# Connectors.net
KiCad netlist of a schematic drawn in Altium Designer
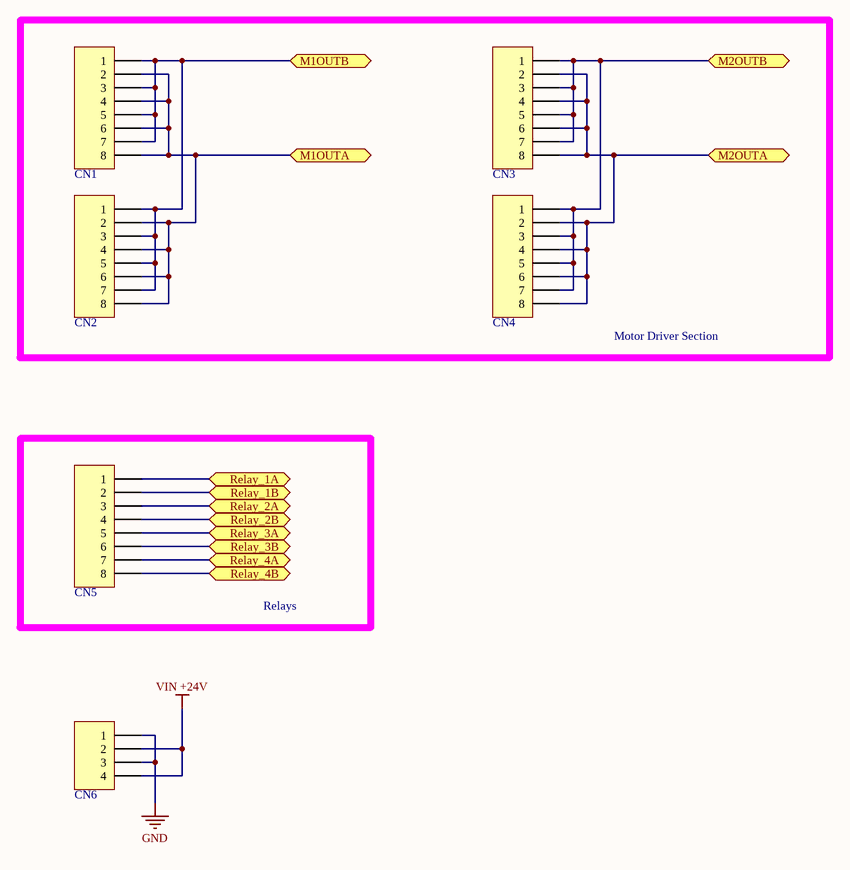
[diagram p0: Connectors.SchDoc]

(export (version "E")
  (design (tool "Eeschema 10.0.6"))
  (components
    (comp (ref "CN1")
      (value "Connector 4973-08TRNLF")
      (footprint "Connector 4973-08TRNLF")
      (description "Connector 8-Pin, 90 degree, 3.5mm")
      (libsource (lib "Erdem_05112012") (part "Connector 4973-08TRNLF"))
    )
    (comp (ref "CN2")
      (value "Connector 4973-08TRNLF")
      (footprint "Connector 4973-08TRNLF")
      (description "Connector 8-Pin, 90 degree, 3.5mm")
      (libsource (lib "Erdem_05112012") (part "Connector 4973-08TRNLF"))
    )
    (comp (ref "CN3")
      (value "Connector 4973-08TRNLF")
      (footprint "Connector 4973-08TRNLF")
      (description "Connector 8-Pin, 90 degree, 3.5mm")
      (libsource (lib "Erdem_05112012") (part "Connector 4973-08TRNLF"))
    )
    (comp (ref "CN4")
      (value "Connector 4973-08TRNLF")
      (footprint "Connector 4973-08TRNLF")
      (description "Connector 8-Pin, 90 degree, 3.5mm")
      (libsource (lib "Erdem_05112012") (part "Connector 4973-08TRNLF"))
    )
    (comp (ref "CN5")
      (value "Connector 4973-08TRNLF")
      (footprint "Connector 4973-08TRNLF")
      (description "Connector 8-Pin, 90 degree, 3.5mm")
      (libsource (lib "Erdem_05112012") (part "Connector 4973-08TRNLF"))
    )
    (comp (ref "CN6")
      (value "Connector 4973-04TRNLF")
      (footprint "Connector 4973-04TRNLF")
      (description "Connector 4-Pin, 90 degree, 3.5mm")
      (libsource (lib "Erdem_05112012") (part "Connector 4973-04TRNLF"))
    )
  )
  (nets
    (net (code "1") (name "/M1OUTA") (class "Default")
      (node (ref "CN1") (pin "2") (pinfunction "2_2") (pintype "passive"))
      (node (ref "CN1") (pin "4") (pinfunction "4_4") (pintype "passive"))
      (node (ref "CN1") (pin "6") (pinfunction "6_6") (pintype "passive"))
      (node (ref "CN1") (pin "8") (pinfunction "8_8") (pintype "passive"))
      (node (ref "CN2") (pin "2") (pinfunction "2_2") (pintype "passive"))
      (node (ref "CN2") (pin "4") (pinfunction "4_4") (pintype "passive"))
      (node (ref "CN2") (pin "6") (pinfunction "6_6") (pintype "passive"))
      (node (ref "CN2") (pin "8") (pinfunction "8_8") (pintype "passive"))
    )
    (net (code "2") (name "/M1OUTB") (class "Default")
      (node (ref "CN1") (pin "1") (pinfunction "1_1") (pintype "passive"))
      (node (ref "CN1") (pin "3") (pinfunction "3_3") (pintype "passive"))
      (node (ref "CN1") (pin "5") (pinfunction "5_5") (pintype "passive"))
      (node (ref "CN1") (pin "7") (pinfunction "7_7") (pintype "passive"))
      (node (ref "CN2") (pin "1") (pinfunction "1_1") (pintype "passive"))
      (node (ref "CN2") (pin "3") (pinfunction "3_3") (pintype "passive"))
      (node (ref "CN2") (pin "5") (pinfunction "5_5") (pintype "passive"))
      (node (ref "CN2") (pin "7") (pinfunction "7_7") (pintype "passive"))
    )
    (net (code "3") (name "/M2OUTA") (class "Default")
      (node (ref "CN3") (pin "2") (pinfunction "2_2") (pintype "passive"))
      (node (ref "CN3") (pin "4") (pinfunction "4_4") (pintype "passive"))
      (node (ref "CN3") (pin "6") (pinfunction "6_6") (pintype "passive"))
      (node (ref "CN3") (pin "8") (pinfunction "8_8") (pintype "passive"))
      (node (ref "CN4") (pin "2") (pinfunction "2_2") (pintype "passive"))
      (node (ref "CN4") (pin "4") (pinfunction "4_4") (pintype "passive"))
      (node (ref "CN4") (pin "6") (pinfunction "6_6") (pintype "passive"))
      (node (ref "CN4") (pin "8") (pinfunction "8_8") (pintype "passive"))
    )
    (net (code "4") (name "/M2OUTB") (class "Default")
      (node (ref "CN3") (pin "1") (pinfunction "1_1") (pintype "passive"))
      (node (ref "CN3") (pin "3") (pinfunction "3_3") (pintype "passive"))
      (node (ref "CN3") (pin "5") (pinfunction "5_5") (pintype "passive"))
      (node (ref "CN3") (pin "7") (pinfunction "7_7") (pintype "passive"))
      (node (ref "CN4") (pin "1") (pinfunction "1_1") (pintype "passive"))
      (node (ref "CN4") (pin "3") (pinfunction "3_3") (pintype "passive"))
      (node (ref "CN4") (pin "5") (pinfunction "5_5") (pintype "passive"))
      (node (ref "CN4") (pin "7") (pinfunction "7_7") (pintype "passive"))
    )
    (net (code "5") (name "/Relay_1A") (class "Default")
      (node (ref "CN5") (pin "1") (pinfunction "1_1") (pintype "passive"))
    )
    (net (code "6") (name "/Relay_1B") (class "Default")
      (node (ref "CN5") (pin "2") (pinfunction "2_2") (pintype "passive"))
    )
    (net (code "7") (name "/Relay_2A") (class "Default")
      (node (ref "CN5") (pin "3") (pinfunction "3_3") (pintype "passive"))
    )
    (net (code "8") (name "/Relay_2B") (class "Default")
      (node (ref "CN5") (pin "4") (pinfunction "4_4") (pintype "passive"))
    )
    (net (code "9") (name "/Relay_3A") (class "Default")
      (node (ref "CN5") (pin "5") (pinfunction "5_5") (pintype "passive"))
    )
    (net (code "10") (name "/Relay_3B") (class "Default")
      (node (ref "CN5") (pin "6") (pinfunction "6_6") (pintype "passive"))
    )
    (net (code "11") (name "/Relay_4A") (class "Default")
      (node (ref "CN5") (pin "7") (pinfunction "7_7") (pintype "passive"))
    )
    (net (code "12") (name "/Relay_4B") (class "Default")
      (node (ref "CN5") (pin "8") (pinfunction "8_8") (pintype "passive"))
    )
    (net (code "13") (name "GND") (class "Default")
      (node (ref "CN6") (pin "1") (pinfunction "1_1") (pintype "passive"))
      (node (ref "CN6") (pin "3") (pinfunction "3_3") (pintype "passive"))
    )
    (net (code "14") (name "VIN +24V") (class "Default")
      (node (ref "CN6") (pin "2") (pinfunction "2_2") (pintype "passive"))
      (node (ref "CN6") (pin "4") (pinfunction "4_4") (pintype "passive"))
    )
  )
)
